# W7500S2E-X1.net
KiCad netlist of a schematic drawn in Altium Designer
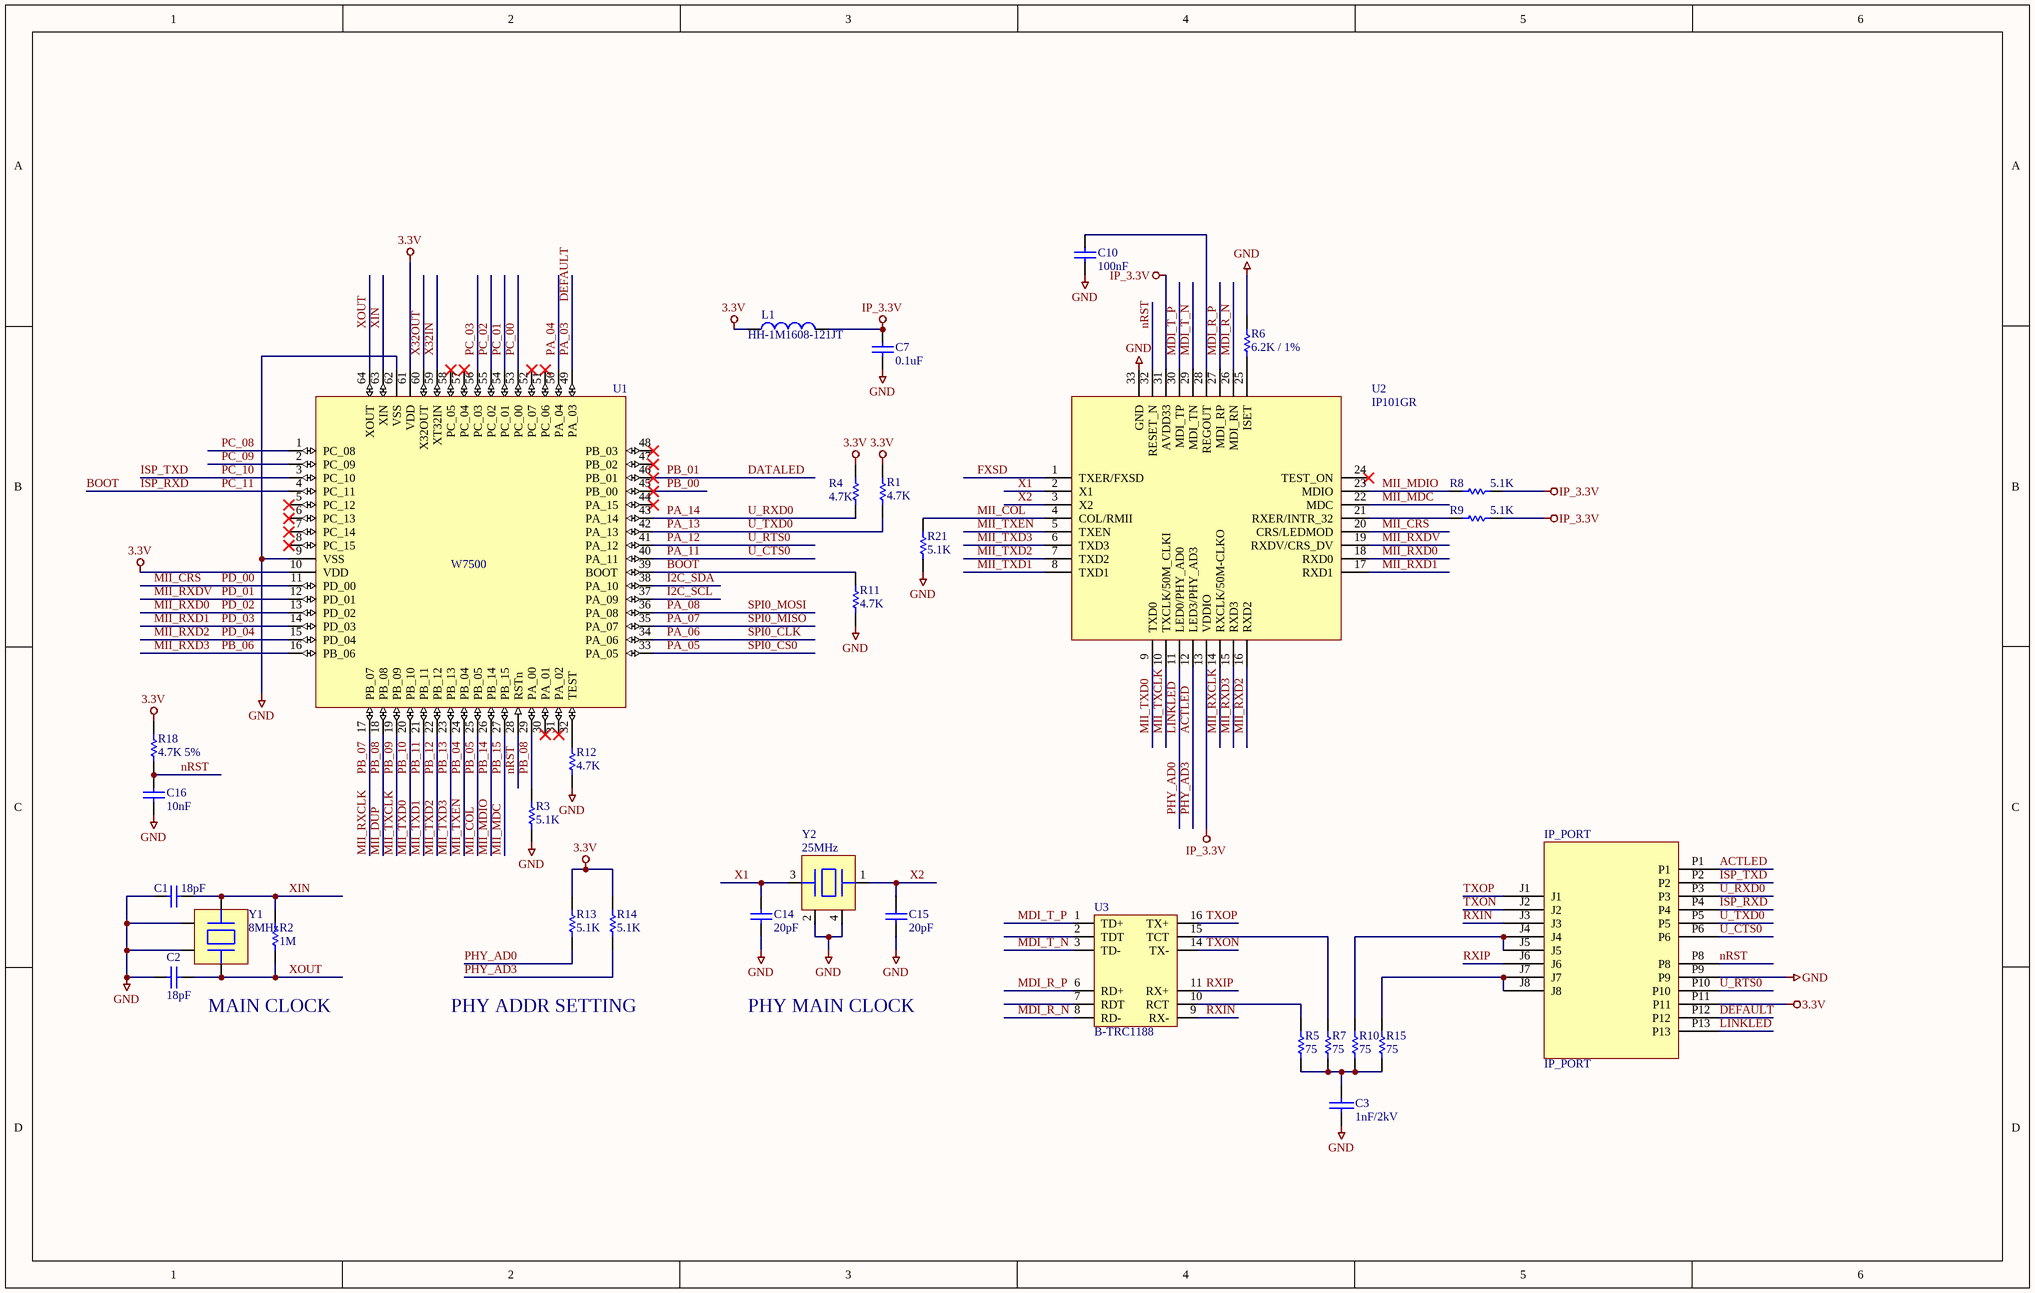
[diagram p0: W7500S2E-X1.SchDoc]

(export (version "E")
  (design (tool "Eeschema 10.0.6"))
  (components
    (comp (ref "C1")
      (value "18pF")
      (footprint "CAP-0402")
      (description "CAP-0402")
      (libsource (lib "Scott_lib") (part "CAP-0402"))
    )
    (comp (ref "C2")
      (value "18pF")
      (footprint "CAP-0402")
      (description "CAP-0402")
      (libsource (lib "Scott_lib") (part "CAP-0402"))
    )
    (comp (ref "C3")
      (value "1nF/2kV")
      (footprint "1206-C - SMD")
      (description "Capacitor")
      (libsource (lib "*") (part "CAP"))
    )
    (comp (ref "C7")
      (value "0.1uF")
      (footprint "CAP-0402")
      (description "CAP-0402")
      (libsource (lib "Scott_lib") (part "CAP-0402"))
    )
    (comp (ref "C10")
      (value "100nF")
      (footprint "CAP-0402")
      (description "CAP-0402")
      (libsource (lib "Scott_lib") (part "CAP-0402"))
    )
    (comp (ref "C14")
      (value "20pF")
      (footprint "CAP-0402")
      (description "CAP-0402")
      (libsource (lib "Scott_lib") (part "CAP-0402"))
    )
    (comp (ref "C15")
      (value "20pF")
      (footprint "CAP-0402")
      (description "CAP-0402")
      (libsource (lib "Scott_lib") (part "CAP-0402"))
    )
    (comp (ref "C16")
      (value "10nF")
      (footprint "CAP-0402")
      (description "CAP-0402")
      (libsource (lib "Scott_lib") (part "CAP-0402"))
    )
    (comp (ref "IP_PORT")
      (value "IP_PORT")
      (footprint "IP_PORT")
      (libsource (lib "IP_PORT") (part "IP_PORT"))
    )
    (comp (ref "L1")
      (value "HH-1M1608-121JT")
      (footprint "IND-0603")
      (description "Inductor 0603(1608)")
      (libsource (lib "Scott_lib") (part "IND-0603"))
    )
    (comp (ref "R1")
      (value "4.7K")
      (footprint "RES-0402")
      (description "RES-0402")
      (libsource (lib "Scott_lib") (part "RES-0402"))
    )
    (comp (ref "R2")
      (value "1M")
      (footprint "RES-0402")
      (description "RES-0402")
      (libsource (lib "Scott_lib") (part "RES-0402"))
    )
    (comp (ref "R3")
      (value "5.1K")
      (footprint "RES-0402")
      (description "RES-0402")
      (libsource (lib "Scott_lib") (part "RES-0402"))
    )
    (comp (ref "R4")
      (value "4.7K")
      (footprint "RES-0402")
      (description "RES-0402")
      (libsource (lib "Scott_lib") (part "RES-0402"))
    )
    (comp (ref "R5")
      (value "75")
      (footprint "RES-0402")
      (description "RES-0402")
      (libsource (lib "Scott_lib") (part "RES-0402"))
    )
    (comp (ref "R6")
      (value "6.2K / 1%")
      (footprint "RES-0402")
      (description "RES-0402")
      (libsource (lib "Scott_lib") (part "RES-0402"))
    )
    (comp (ref "R7")
      (value "75")
      (footprint "RES-0402")
      (description "RES-0402")
      (libsource (lib "Scott_lib") (part "RES-0402"))
    )
    (comp (ref "R8")
      (value "5.1K")
      (footprint "RES-0402")
      (description "RES-0402")
      (libsource (lib "Scott_lib") (part "RES-0402"))
    )
    (comp (ref "R9")
      (value "5.1K")
      (footprint "RES-0402")
      (description "RES-0402")
      (libsource (lib "Scott_lib") (part "RES-0402"))
    )
    (comp (ref "R10")
      (value "75")
      (footprint "RES-0402")
      (description "RES-0402")
      (libsource (lib "Scott_lib") (part "RES-0402"))
    )
    (comp (ref "R11")
      (value "4.7K")
      (footprint "RES-0402")
      (description "RES-0402")
      (libsource (lib "Scott_lib") (part "RES-0402"))
    )
    (comp (ref "R12")
      (value "4.7K")
      (footprint "RES-0402")
      (description "RES-0402")
      (libsource (lib "Scott_lib") (part "RES-0402"))
    )
    (comp (ref "R13")
      (value "5.1K")
      (footprint "RES-0402")
      (description "RES-0402")
      (libsource (lib "Scott_lib") (part "RES-0402"))
    )
    (comp (ref "R14")
      (value "5.1K")
      (footprint "RES-0402")
      (description "RES-0402")
      (libsource (lib "Scott_lib") (part "RES-0402"))
    )
    (comp (ref "R15")
      (value "75")
      (footprint "RES-0402")
      (description "RES-0402")
      (libsource (lib "Scott_lib") (part "RES-0402"))
    )
    (comp (ref "R18")
      (value "4.7K 5%")
      (footprint "RES-0402")
      (description "Resistor")
      (fields (field (name "Comment") "Res1") (field (name "PUBLISHER") "Altium Limited"))
      (libsource (lib "Miscellaneous Devices") (part "Res1"))
    )
    (comp (ref "R21")
      (value "5.1K")
      (footprint "RES-0402")
      (description "RES-0402")
      (libsource (lib "Scott_lib") (part "RES-0402"))
    )
    (comp (ref "U1")
      (value "W7500")
      (footprint "W7500-LQFP64")
      (description "WIZnet ARM Cortex-M0")
      (libsource (lib "Scott_lib") (part "W7500"))
    )
    (comp (ref "U2")
      (value "IP101GR")
      (footprint "QFN32(4X4mm)")
      (libsource (lib "IP101GR") (part "IP101GR"))
    )
    (comp (ref "U3")
      (value "B-TRC1188")
      (footprint "11FB-05NL")
      (libsource (lib "11FB-05NL") (part "11FB-05NL"))
    )
    (comp (ref "Y1")
      (value "8MHz")
      (footprint "OSC-TZ1067B")
      (description "X-tal 25MHz,3.2x2.5 SMD, CL=18pF")
      (libsource (lib "") (part "82J0626-25MHz_1"))
    )
    (comp (ref "Y2")
      (value "25MHz")
      (footprint "OSC-TZ1067B")
      (description "X-tal 25MHz,3.2x2.5 SMD, CL=18pF")
      (libsource (lib "Scott_lib") (part "82J0626-25MHz"))
    )
  )
  (nets
    (net (code "1") (name "/ACTLED") (class "Default")
      (node (ref "IP_PORT") (pin "P1") (pinfunction "P1_P1") (pintype "passive"))
      (node (ref "R14") (pin "1") (pinfunction "1_1") (pintype "passive"))
      (node (ref "U2") (pin "12") (pinfunction "LED3/PHY_AD3_12") (pintype "passive"))
    )
    (net (code "2") (name "/BOOT") (class "Default")
      (node (ref "IP_PORT") (pin "P4") (pinfunction "P4_P4") (pintype "passive"))
      (node (ref "R11") (pin "2") (pinfunction "2_2") (pintype "passive"))
      (node (ref "U1") (pin "39") (pinfunction "BOOT_39") (pintype "bidirectional"))
      (node (ref "U1") (pin "4") (pinfunction "PC_11_4") (pintype "bidirectional"))
    )
    (net (code "3") (name "/DATALED") (class "Default")
      (node (ref "U1") (pin "46") (pinfunction "PB_01_46") (pintype "bidirectional+no_connect"))
    )
    (net (code "4") (name "/DEFAULT") (class "Default")
      (node (ref "IP_PORT") (pin "P12") (pinfunction "P12_P12") (pintype "passive"))
      (node (ref "U1") (pin "49") (pinfunction "PA_03_49") (pintype "bidirectional"))
    )
    (net (code "5") (name "/FXSD") (class "Default")
      (node (ref "U2") (pin "1") (pinfunction "TXER/FXSD_1") (pintype "passive"))
    )
    (net (code "6") (name "/I2C_SCL") (class "Default")
      (node (ref "U1") (pin "37") (pinfunction "PA_09_37") (pintype "bidirectional"))
    )
    (net (code "7") (name "/I2C_SDA") (class "Default")
      (node (ref "U1") (pin "38") (pinfunction "PA_10_38") (pintype "bidirectional"))
    )
    (net (code "8") (name "/ISP_TXD") (class "Default")
      (node (ref "IP_PORT") (pin "P2") (pinfunction "P2_P2") (pintype "passive"))
      (node (ref "U1") (pin "3") (pinfunction "PC_10_3") (pintype "bidirectional"))
    )
    (net (code "9") (name "/LINKLED") (class "Default")
      (node (ref "IP_PORT") (pin "P13") (pinfunction "P13_P13") (pintype "passive"))
      (node (ref "R13") (pin "1") (pinfunction "1_1") (pintype "passive"))
      (node (ref "U2") (pin "11") (pinfunction "LED0/PHY_AD0_11") (pintype "passive"))
    )
    (net (code "10") (name "/MDI_R_N") (class "Default")
      (node (ref "U2") (pin "26") (pinfunction "MDI_RN_26") (pintype "passive"))
      (node (ref "U3") (pin "8") (pinfunction "RD-_8") (pintype "passive"))
    )
    (net (code "11") (name "/MDI_R_P") (class "Default")
      (node (ref "U2") (pin "27") (pinfunction "MDI_RP_27") (pintype "passive"))
      (node (ref "U3") (pin "6") (pinfunction "RD+_6") (pintype "passive"))
    )
    (net (code "12") (name "/MDI_T_N") (class "Default")
      (node (ref "U2") (pin "29") (pinfunction "MDI_TN_29") (pintype "passive"))
      (node (ref "U3") (pin "3") (pinfunction "TD-_3") (pintype "passive"))
    )
    (net (code "13") (name "/MDI_T_P") (class "Default")
      (node (ref "U2") (pin "30") (pinfunction "MDI_TP_30") (pintype "passive"))
      (node (ref "U3") (pin "1") (pinfunction "TD+_1") (pintype "passive"))
    )
    (net (code "14") (name "/MII_COL") (class "Default")
      (node (ref "R21") (pin "2") (pinfunction "2_2") (pintype "passive"))
      (node (ref "U1") (pin "25") (pinfunction "PB_05_25") (pintype "bidirectional"))
      (node (ref "U2") (pin "4") (pinfunction "COL/RMII_4") (pintype "passive"))
    )
    (net (code "15") (name "/MII_CRS") (class "Default")
      (node (ref "U1") (pin "11") (pinfunction "PD_00_11") (pintype "bidirectional"))
      (node (ref "U2") (pin "20") (pinfunction "CRS/LEDMOD_20") (pintype "passive"))
    )
    (net (code "16") (name "/MII_DUP") (class "Default")
      (node (ref "R3") (pin "2") (pinfunction "2_2") (pintype "passive"))
      (node (ref "U1") (pin "18") (pinfunction "PB_08_18") (pintype "bidirectional"))
      (node (ref "U1") (pin "29") (pinfunction "PA_00_29") (pintype "bidirectional"))
    )
    (net (code "17") (name "/MII_MDC") (class "Default")
      (node (ref "U1") (pin "27") (pinfunction "PB_15_27") (pintype "bidirectional"))
      (node (ref "U2") (pin "22") (pinfunction "MDC_22") (pintype "passive"))
    )
    (net (code "18") (name "/MII_MDIO") (class "Default")
      (node (ref "R8") (pin "2") (pinfunction "2_2") (pintype "passive"))
      (node (ref "U1") (pin "26") (pinfunction "PB_14_26") (pintype "bidirectional"))
      (node (ref "U2") (pin "23") (pinfunction "MDIO_23") (pintype "passive"))
    )
    (net (code "19") (name "/MII_RXCLK") (class "Default")
      (node (ref "U1") (pin "17") (pinfunction "PB_07_17") (pintype "bidirectional"))
      (node (ref "U2") (pin "14") (pinfunction "RXCLK/50M-CLKO_14") (pintype "passive"))
    )
    (net (code "20") (name "/MII_RXD0") (class "Default")
      (node (ref "U1") (pin "13") (pinfunction "PD_02_13") (pintype "bidirectional"))
      (node (ref "U2") (pin "18") (pinfunction "RXD0_18") (pintype "passive"))
    )
    (net (code "21") (name "/MII_RXD1") (class "Default")
      (node (ref "U1") (pin "14") (pinfunction "PD_03_14") (pintype "bidirectional"))
      (node (ref "U2") (pin "17") (pinfunction "RXD1_17") (pintype "passive"))
    )
    (net (code "22") (name "/MII_RXD2") (class "Default")
      (node (ref "U1") (pin "15") (pinfunction "PD_04_15") (pintype "bidirectional"))
      (node (ref "U2") (pin "16") (pinfunction "RXD2_16") (pintype "passive"))
    )
    (net (code "23") (name "/MII_RXD3") (class "Default")
      (node (ref "U1") (pin "16") (pinfunction "PB_06_16") (pintype "bidirectional"))
      (node (ref "U2") (pin "15") (pinfunction "RXD3_15") (pintype "passive"))
    )
    (net (code "24") (name "/MII_RXDV") (class "Default")
      (node (ref "U1") (pin "12") (pinfunction "PD_01_12") (pintype "bidirectional"))
      (node (ref "U2") (pin "19") (pinfunction "RXDV/CRS_DV_19") (pintype "passive"))
    )
    (net (code "25") (name "/MII_TXCLK") (class "Default")
      (node (ref "U1") (pin "19") (pinfunction "PB_09_19") (pintype "bidirectional"))
      (node (ref "U2") (pin "10") (pinfunction "TXCLK/50M_CLKI_10") (pintype "passive"))
    )
    (net (code "26") (name "/MII_TXD0") (class "Default")
      (node (ref "U1") (pin "20") (pinfunction "PB_10_20") (pintype "bidirectional"))
      (node (ref "U2") (pin "9") (pinfunction "TXD0_9") (pintype "passive"))
    )
    (net (code "27") (name "/MII_TXD1") (class "Default")
      (node (ref "U1") (pin "21") (pinfunction "PB_11_21") (pintype "bidirectional"))
      (node (ref "U2") (pin "8") (pinfunction "TXD1_8") (pintype "passive"))
    )
    (net (code "28") (name "/MII_TXD2") (class "Default")
      (node (ref "U1") (pin "22") (pinfunction "PB_12_22") (pintype "bidirectional"))
      (node (ref "U2") (pin "7") (pinfunction "TXD2_7") (pintype "passive"))
    )
    (net (code "29") (name "/MII_TXD3") (class "Default")
      (node (ref "U1") (pin "23") (pinfunction "PB_13_23") (pintype "bidirectional"))
      (node (ref "U2") (pin "6") (pinfunction "TXD3_6") (pintype "passive"))
    )
    (net (code "30") (name "/MII_TXEN") (class "Default")
      (node (ref "U1") (pin "24") (pinfunction "PB_04_24") (pintype "bidirectional"))
      (node (ref "U2") (pin "5") (pinfunction "TXEN_5") (pintype "passive"))
    )
    (net (code "31") (name "/PA_04") (class "Default")
      (node (ref "U1") (pin "50") (pinfunction "PA_04_50") (pintype "bidirectional"))
    )
    (net (code "32") (name "/PA_05") (class "Default")
      (node (ref "U1") (pin "33") (pinfunction "PA_05_33") (pintype "bidirectional"))
    )
    (net (code "33") (name "/PA_06") (class "Default")
      (node (ref "U1") (pin "34") (pinfunction "PA_06_34") (pintype "bidirectional"))
    )
    (net (code "34") (name "/PA_07") (class "Default")
      (node (ref "U1") (pin "35") (pinfunction "PA_07_35") (pintype "bidirectional"))
    )
    (net (code "35") (name "/PA_08") (class "Default")
      (node (ref "U1") (pin "36") (pinfunction "PA_08_36") (pintype "bidirectional"))
    )
    (net (code "36") (name "/PA_11") (class "Default")
      (node (ref "IP_PORT") (pin "P6") (pinfunction "P6_P6") (pintype "passive"))
      (node (ref "U1") (pin "40") (pinfunction "PA_11_40") (pintype "bidirectional"))
    )
    (net (code "37") (name "/PA_12") (class "Default")
      (node (ref "IP_PORT") (pin "P10") (pinfunction "P10_P10") (pintype "passive"))
      (node (ref "U1") (pin "41") (pinfunction "PA_12_41") (pintype "bidirectional"))
    )
    (net (code "38") (name "/PA_13") (class "Default")
      (node (ref "IP_PORT") (pin "P5") (pinfunction "P5_P5") (pintype "passive"))
      (node (ref "R1") (pin "2") (pinfunction "2_2") (pintype "passive"))
      (node (ref "U1") (pin "42") (pinfunction "PA_13_42") (pintype "bidirectional"))
    )
    (net (code "39") (name "/PA_14") (class "Default")
      (node (ref "IP_PORT") (pin "P3") (pinfunction "P3_P3") (pintype "passive"))
      (node (ref "R4") (pin "2") (pinfunction "2_2") (pintype "passive"))
      (node (ref "U1") (pin "43") (pinfunction "PA_14_43") (pintype "bidirectional"))
    )
    (net (code "40") (name "/PB_00") (class "Default")
      (node (ref "U1") (pin "45") (pinfunction "PB_00_45") (pintype "bidirectional+no_connect"))
    )
    (net (code "41") (name "/PC_00") (class "Default")
      (node (ref "U1") (pin "53") (pinfunction "PC_00_53") (pintype "bidirectional"))
    )
    (net (code "42") (name "/PC_01") (class "Default")
      (node (ref "U1") (pin "54") (pinfunction "PC_01_54") (pintype "bidirectional"))
    )
    (net (code "43") (name "/PC_02") (class "Default")
      (node (ref "U1") (pin "55") (pinfunction "PC_02_55") (pintype "bidirectional"))
    )
    (net (code "44") (name "/PC_03") (class "Default")
      (node (ref "U1") (pin "56") (pinfunction "PC_03_56") (pintype "bidirectional"))
    )
    (net (code "45") (name "/PC_08") (class "Default")
      (node (ref "U1") (pin "1") (pinfunction "PC_08_1") (pintype "bidirectional"))
    )
    (net (code "46") (name "/PC_09") (class "Default")
      (node (ref "U1") (pin "2") (pinfunction "PC_09_2") (pintype "bidirectional"))
    )
    (net (code "47") (name "/RXIN") (class "Default")
      (node (ref "IP_PORT") (pin "J3") (pinfunction "J3_J3") (pintype "passive"))
      (node (ref "U3") (pin "9") (pinfunction "RX-_9") (pintype "passive"))
    )
    (net (code "48") (name "/RXIP") (class "Default")
      (node (ref "IP_PORT") (pin "J6") (pinfunction "J6_J6") (pintype "passive"))
      (node (ref "U3") (pin "11") (pinfunction "RX+_11") (pintype "passive"))
    )
    (net (code "49") (name "/TXON") (class "Default")
      (node (ref "IP_PORT") (pin "J2") (pinfunction "J2_J2") (pintype "passive"))
      (node (ref "U3") (pin "14") (pinfunction "TX-_14") (pintype "passive"))
    )
    (net (code "50") (name "/TXOP") (class "Default")
      (node (ref "IP_PORT") (pin "J1") (pinfunction "J1_J1") (pintype "passive"))
      (node (ref "U3") (pin "16") (pinfunction "TX+_16") (pintype "passive"))
    )
    (net (code "51") (name "/X1") (class "Default")
      (node (ref "C14") (pin "2") (pinfunction "2_2") (pintype "passive"))
      (node (ref "U2") (pin "2") (pinfunction "X1_2") (pintype "passive"))
      (node (ref "Y2") (pin "3") (pinfunction "3_3") (pintype "passive"))
    )
    (net (code "52") (name "/X2") (class "Default")
      (node (ref "C15") (pin "2") (pinfunction "2_2") (pintype "passive"))
      (node (ref "U2") (pin "3") (pinfunction "X2_3") (pintype "passive"))
      (node (ref "Y2") (pin "1") (pinfunction "1_1") (pintype "passive"))
    )
    (net (code "53") (name "/X32IN") (class "Default")
      (node (ref "U1") (pin "59") (pinfunction "XT32IN_59") (pintype "bidirectional"))
    )
    (net (code "54") (name "/X32OUT") (class "Default")
      (node (ref "U1") (pin "60") (pinfunction "X32OUT_60") (pintype "bidirectional"))
    )
    (net (code "55") (name "/XIN") (class "Default")
      (node (ref "C1") (pin "2") (pinfunction "2_2") (pintype "passive"))
      (node (ref "R2") (pin "1") (pinfunction "1_1") (pintype "passive"))
      (node (ref "U1") (pin "63") (pinfunction "XIN_63") (pintype "bidirectional"))
      (node (ref "Y1") (pin "3") (pinfunction "3_3") (pintype "passive"))
    )
    (net (code "56") (name "/XOUT") (class "Default")
      (node (ref "C2") (pin "2") (pinfunction "2_2") (pintype "passive"))
      (node (ref "R2") (pin "2") (pinfunction "2_2") (pintype "passive"))
      (node (ref "U1") (pin "64") (pinfunction "XOUT_64") (pintype "bidirectional"))
      (node (ref "Y1") (pin "1") (pinfunction "1_1") (pintype "passive"))
    )
    (net (code "57") (name "/nRST") (class "Default")
      (node (ref "C16") (pin "2") (pinfunction "2_2") (pintype "passive"))
      (node (ref "IP_PORT") (pin "P8") (pinfunction "P8_P8") (pintype "passive"))
      (node (ref "R18") (pin "1") (pinfunction "1_1") (pintype "passive"))
      (node (ref "U1") (pin "28") (pinfunction "RSTn_28") (pintype "input"))
      (node (ref "U2") (pin "32") (pinfunction "RESET_N_32") (pintype "passive"))
    )
    (net (code "58") (name "3.3V") (class "Default")
      (node (ref "IP_PORT") (pin "P11") (pinfunction "P11_P11") (pintype "passive"))
      (node (ref "L1") (pin "1") (pinfunction "1_1") (pintype "passive"))
      (node (ref "R1") (pin "1") (pinfunction "1_1") (pintype "passive"))
      (node (ref "R13") (pin "2") (pinfunction "2_2") (pintype "passive"))
      (node (ref "R14") (pin "2") (pinfunction "2_2") (pintype "passive"))
      (node (ref "R18") (pin "2") (pinfunction "2_2") (pintype "passive"))
      (node (ref "R4") (pin "1") (pinfunction "1_1") (pintype "passive"))
      (node (ref "U1") (pin "10") (pinfunction "VDD_10") (pintype "power_in"))
      (node (ref "U1") (pin "61") (pinfunction "VDD_61") (pintype "power_in"))
    )
    (net (code "59") (name "GND") (class "Default")
      (node (ref "C1") (pin "1") (pinfunction "1_1") (pintype "passive"))
      (node (ref "C10") (pin "1") (pinfunction "1_1") (pintype "passive"))
      (node (ref "C14") (pin "1") (pinfunction "1_1") (pintype "passive"))
      (node (ref "C15") (pin "1") (pinfunction "1_1") (pintype "passive"))
      (node (ref "C16") (pin "1") (pinfunction "1_1") (pintype "passive"))
      (node (ref "C2") (pin "1") (pinfunction "1_1") (pintype "passive"))
      (node (ref "C3") (pin "1") (pinfunction "1_1") (pintype "passive"))
      (node (ref "C7") (pin "1") (pinfunction "1_1") (pintype "passive"))
      (node (ref "IP_PORT") (pin "P9") (pinfunction "P9_P9") (pintype "passive"))
      (node (ref "R11") (pin "1") (pinfunction "1_1") (pintype "passive"))
      (node (ref "R12") (pin "1") (pinfunction "1_1") (pintype "passive"))
      (node (ref "R21") (pin "1") (pinfunction "1_1") (pintype "passive"))
      (node (ref "R3") (pin "1") (pinfunction "1_1") (pintype "passive"))
      (node (ref "R6") (pin "2") (pinfunction "2_2") (pintype "passive"))
      (node (ref "U1") (pin "62") (pinfunction "VSS_62") (pintype "power_in"))
      (node (ref "U1") (pin "9") (pinfunction "VSS_9") (pintype "power_in"))
      (node (ref "U2") (pin "33") (pinfunction "GND_33") (pintype "passive"))
      (node (ref "Y1") (pin "2") (pinfunction "2_2") (pintype "passive"))
      (node (ref "Y1") (pin "4") (pinfunction "4_4") (pintype "passive"))
      (node (ref "Y2") (pin "2") (pinfunction "2_2") (pintype "passive"))
      (node (ref "Y2") (pin "4") (pinfunction "4_4") (pintype "passive"))
    )
    (net (code "60") (name "IP_3.3V") (class "Default")
      (node (ref "C7") (pin "2") (pinfunction "2_2") (pintype "passive"))
      (node (ref "L1") (pin "2") (pinfunction "2_2") (pintype "passive"))
      (node (ref "R8") (pin "1") (pinfunction "1_1") (pintype "passive"))
      (node (ref "R9") (pin "1") (pinfunction "1_1") (pintype "passive"))
      (node (ref "U2") (pin "13") (pinfunction "VDDIO_13") (pintype "passive"))
      (node (ref "U2") (pin "31") (pinfunction "AVDD33_31") (pintype "passive"))
    )
    (net (code "61") (name "Net-(C3-Pad2)") (class "Default")
      (node (ref "C3") (pin "2") (pinfunction "2_2") (pintype "passive"))
      (node (ref "R10") (pin "2") (pinfunction "2_2") (pintype "passive"))
      (node (ref "R15") (pin "2") (pinfunction "2_2") (pintype "passive"))
      (node (ref "R5") (pin "2") (pinfunction "2_2") (pintype "passive"))
      (node (ref "R7") (pin "2") (pinfunction "2_2") (pintype "passive"))
    )
    (net (code "62") (name "Net-(IP_PORT-PadJ4)") (class "Default")
      (node (ref "IP_PORT") (pin "J4") (pinfunction "J4_J4") (pintype "passive"))
      (node (ref "IP_PORT") (pin "J5") (pinfunction "J5_J5") (pintype "passive"))
      (node (ref "R10") (pin "1") (pinfunction "1_1") (pintype "passive"))
    )
    (net (code "63") (name "Net-(IP_PORT-PadJ7)") (class "Default")
      (node (ref "IP_PORT") (pin "J7") (pinfunction "J7_J7") (pintype "passive"))
      (node (ref "IP_PORT") (pin "J8") (pinfunction "J8_J8") (pintype "passive"))
      (node (ref "R15") (pin "1") (pinfunction "1_1") (pintype "passive"))
    )
    (net (code "64") (name "Net-(U1-TEST)") (class "Default")
      (node (ref "R12") (pin "2") (pinfunction "2_2") (pintype "passive"))
      (node (ref "U1") (pin "32") (pinfunction "TEST_32") (pintype "bidirectional"))
    )
    (net (code "65") (name "Net-(U2-ISET)") (class "Default")
      (node (ref "R6") (pin "1") (pinfunction "1_1") (pintype "passive"))
      (node (ref "U2") (pin "25") (pinfunction "ISET_25") (pintype "passive"))
    )
    (net (code "66") (name "Net-(U2-REGOUT)") (class "Default")
      (node (ref "C10") (pin "2") (pinfunction "2_2") (pintype "passive"))
      (node (ref "U2") (pin "28") (pinfunction "REGOUT_28") (pintype "passive"))
    )
    (net (code "67") (name "Net-(U2-RXER{slash}INTR_32)") (class "Default")
      (node (ref "R9") (pin "2") (pinfunction "2_2") (pintype "passive"))
      (node (ref "U2") (pin "21") (pinfunction "RXER/INTR_32_21") (pintype "passive"))
    )
    (net (code "68") (name "Net-(U3-RCT)") (class "Default")
      (node (ref "R5") (pin "1") (pinfunction "1_1") (pintype "passive"))
      (node (ref "U3") (pin "10") (pinfunction "RCT_10") (pintype "passive"))
    )
    (net (code "69") (name "Net-(U3-TCT)") (class "Default")
      (node (ref "R7") (pin "1") (pinfunction "1_1") (pintype "passive"))
      (node (ref "U3") (pin "15") (pinfunction "TCT_15") (pintype "passive"))
    )
    (net (code "70") (name "unconnected-(U1-PA_01-Pad30)") (class "Default")
      (node (ref "U1") (pin "30") (pinfunction "PA_01_30") (pintype "bidirectional+no_connect"))
    )
    (net (code "71") (name "unconnected-(U1-PA_02-Pad31)") (class "Default")
      (node (ref "U1") (pin "31") (pinfunction "PA_02_31") (pintype "bidirectional+no_connect"))
    )
    (net (code "72") (name "unconnected-(U1-PA_15-Pad44)") (class "Default")
      (node (ref "U1") (pin "44") (pinfunction "PA_15_44") (pintype "bidirectional+no_connect"))
    )
    (net (code "73") (name "unconnected-(U1-PB_02-Pad47)") (class "Default")
      (node (ref "U1") (pin "47") (pinfunction "PB_02_47") (pintype "bidirectional+no_connect"))
    )
    (net (code "74") (name "unconnected-(U1-PB_03-Pad48)") (class "Default")
      (node (ref "U1") (pin "48") (pinfunction "PB_03_48") (pintype "bidirectional+no_connect"))
    )
    (net (code "75") (name "unconnected-(U1-PC_04-Pad57)") (class "Default")
      (node (ref "U1") (pin "57") (pinfunction "PC_04_57") (pintype "bidirectional+no_connect"))
    )
    (net (code "76") (name "unconnected-(U1-PC_05-Pad58)") (class "Default")
      (node (ref "U1") (pin "58") (pinfunction "PC_05_58") (pintype "bidirectional+no_connect"))
    )
    (net (code "77") (name "unconnected-(U1-PC_06-Pad51)") (class "Default")
      (node (ref "U1") (pin "51") (pinfunction "PC_06_51") (pintype "bidirectional+no_connect"))
    )
    (net (code "78") (name "unconnected-(U1-PC_07-Pad52)") (class "Default")
      (node (ref "U1") (pin "52") (pinfunction "PC_07_52") (pintype "bidirectional+no_connect"))
    )
    (net (code "79") (name "unconnected-(U1-PC_12-Pad5)") (class "Default")
      (node (ref "U1") (pin "5") (pinfunction "PC_12_5") (pintype "bidirectional+no_connect"))
    )
    (net (code "80") (name "unconnected-(U1-PC_13-Pad6)") (class "Default")
      (node (ref "U1") (pin "6") (pinfunction "PC_13_6") (pintype "bidirectional+no_connect"))
    )
    (net (code "81") (name "unconnected-(U1-PC_14-Pad7)") (class "Default")
      (node (ref "U1") (pin "7") (pinfunction "PC_14_7") (pintype "bidirectional+no_connect"))
    )
    (net (code "82") (name "unconnected-(U1-PC_15-Pad8)") (class "Default")
      (node (ref "U1") (pin "8") (pinfunction "PC_15_8") (pintype "bidirectional+no_connect"))
    )
    (net (code "83") (name "unconnected-(U2-TEST_ON-Pad24)") (class "Default")
      (node (ref "U2") (pin "24") (pinfunction "TEST_ON_24") (pintype "passive+no_connect"))
    )
    (net (code "84") (name "unconnected-(U3-RDT-Pad7)") (class "Default")
      (node (ref "U3") (pin "7") (pinfunction "RDT_7") (pintype "passive"))
    )
    (net (code "85") (name "unconnected-(U3-TDT-Pad2)") (class "Default")
      (node (ref "U3") (pin "2") (pinfunction "TDT_2") (pintype "passive"))
    )
  )
)
